# MIC_AND_SPEAKER.net
KiCad netlist of a schematic drawn in Altium Designer
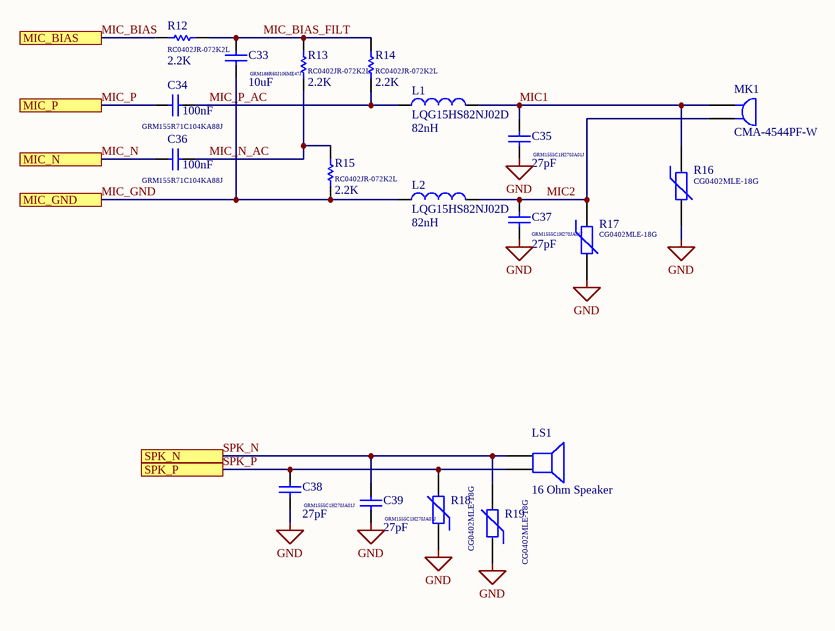
[diagram p0: MIC_AND_SPEAKER.SchDoc]

(export (version "E")
  (design (tool "Eeschema 10.0.6"))
  (components
    (comp (ref "C33")
      (value "GRM188R60J106ME47J")
      (footprint "0402")
      (description "Capacitor")
      (fields (field (name "ALTIUM_VALUE") "10uF") (field (name "PUBLISHER") "Altium Limited"))
      (libsource (lib "Miscellaneous Devices") (part "Cap"))
    )
    (comp (ref "C34")
      (value "GRM155R71C104KA88J")
      (footprint "0402")
      (description "Capacitor")
      (fields (field (name "ALTIUM_VALUE") "100nF") (field (name "PUBLISHER") "Altium Limited"))
      (libsource (lib "Miscellaneous Devices") (part "Cap"))
    )
    (comp (ref "C35")
      (value "GRM1555C1H270JA01J")
      (footprint "0402")
      (description "Capacitor")
      (fields (field (name "ALTIUM_VALUE") "27pF") (field (name "PUBLISHER") "Altium Limited"))
      (libsource (lib "Miscellaneous Devices") (part "Cap"))
    )
    (comp (ref "C36")
      (value "GRM155R71C104KA88J")
      (footprint "0402")
      (description "Capacitor")
      (fields (field (name "ALTIUM_VALUE") "100nF") (field (name "PUBLISHER") "Altium Limited"))
      (libsource (lib "Miscellaneous Devices") (part "Cap"))
    )
    (comp (ref "C37")
      (value "GRM1555C1H270JA01J")
      (footprint "0402")
      (description "Capacitor")
      (fields (field (name "ALTIUM_VALUE") "27pF") (field (name "PUBLISHER") "Altium Limited"))
      (libsource (lib "Miscellaneous Devices") (part "Cap"))
    )
    (comp (ref "C38")
      (value "GRM1555C1H270JA01J")
      (footprint "0402")
      (description "Capacitor")
      (fields (field (name "ALTIUM_VALUE") "27pF") (field (name "PUBLISHER") "Altium Limited"))
      (libsource (lib "Miscellaneous Devices") (part "Cap"))
    )
    (comp (ref "C39")
      (value "GRM1555C1H270JA01J")
      (footprint "0402")
      (description "Capacitor")
      (fields (field (name "ALTIUM_VALUE") "27pF") (field (name "PUBLISHER") "Altium Limited"))
      (libsource (lib "Miscellaneous Devices") (part "Cap"))
    )
    (comp (ref "L1")
      (value "LQG15HS82NJ02D")
      (footprint "0402-A")
      (description "Inductor")
      (fields (field (name "ALTIUM_VALUE") "82nH") (field (name "PUBLISHER") "Altium Limited"))
      (libsource (lib "Miscellaneous Devices") (part "Inductor"))
    )
    (comp (ref "L2")
      (value "LQG15HS82NJ02D")
      (footprint "0402-A")
      (description "Inductor")
      (fields (field (name "ALTIUM_VALUE") "82nH") (field (name "PUBLISHER") "Altium Limited"))
      (libsource (lib "Miscellaneous Devices") (part "Inductor"))
    )
    (comp (ref "LS1")
      (value "16 Ohm Speaker")
      (footprint "PIN2")
      (description "Loudspeaker")
      (fields (field (name "PUBLISHER") "Altium Limited"))
      (libsource (lib "Miscellaneous Devices") (part "Speaker"))
    )
    (comp (ref "MK1")
      (value "CMA-4544PF-W")
      (footprint "PIN2")
      (description "Microphone")
      (fields (field (name "PUBLISHER") "Altium Limited"))
      (libsource (lib "Miscellaneous Devices") (part "Mic1"))
    )
    (comp (ref "R12")
      (value "RC0402JR-072K2L")
      (footprint "0402")
      (description "Resistor")
      (fields (field (name "ALTIUM_VALUE") "2.2K") (field (name "PUBLISHER") "Altium Limited"))
      (libsource (lib "Miscellaneous Devices") (part "Res1"))
    )
    (comp (ref "R13")
      (value "RC0402JR-072K2L")
      (footprint "0402")
      (description "Resistor")
      (fields (field (name "ALTIUM_VALUE") "2.2K") (field (name "PUBLISHER") "Altium Limited"))
      (libsource (lib "Miscellaneous Devices") (part "Res1"))
    )
    (comp (ref "R14")
      (value "RC0402JR-072K2L")
      (footprint "0402")
      (description "Resistor")
      (fields (field (name "ALTIUM_VALUE") "2.2K") (field (name "PUBLISHER") "Altium Limited"))
      (libsource (lib "Miscellaneous Devices") (part "Res1"))
    )
    (comp (ref "R15")
      (value "RC0402JR-072K2L")
      (footprint "0402")
      (description "Resistor")
      (fields (field (name "ALTIUM_VALUE") "2.2K") (field (name "PUBLISHER") "Altium Limited"))
      (libsource (lib "Miscellaneous Devices") (part "Res1"))
    )
    (comp (ref "R16")
      (value "CG0402MLE-18G")
      (footprint "6-0805_N")
      (description "Varistor (Voltage-Sensitive Resistor)")
      (fields (field (name "PUBLISHER") "Altium Limited"))
      (libsource (lib "Miscellaneous Devices") (part "Res Varistor"))
    )
    (comp (ref "R17")
      (value "CG0402MLE-18G")
      (footprint "0402")
      (description "Varistor (Voltage-Sensitive Resistor)")
      (fields (field (name "PUBLISHER") "Altium Limited"))
      (libsource (lib "Miscellaneous Devices") (part "Res Varistor"))
    )
    (comp (ref "R18")
      (value "CG0402MLE-18G")
      (footprint "0402")
      (description "Varistor (Voltage-Sensitive Resistor)")
      (fields (field (name "PUBLISHER") "Altium Limited"))
      (libsource (lib "Miscellaneous Devices") (part "Res Varistor"))
    )
    (comp (ref "R19")
      (value "CG0402MLE-18G")
      (footprint "0402")
      (description "Varistor (Voltage-Sensitive Resistor)")
      (fields (field (name "PUBLISHER") "Altium Limited"))
      (libsource (lib "Miscellaneous Devices") (part "Res Varistor"))
    )
  )
  (nets
    (net (code "1") (name "/MIC1") (class "Default")
      (node (ref "C35") (pin "2") (pinfunction "2_2") (pintype "passive"))
      (node (ref "L1") (pin "2") (pinfunction "2_2") (pintype "passive"))
      (node (ref "MK1") (pin "1") (pinfunction "1_1") (pintype "passive"))
      (node (ref "R16") (pin "1") (pinfunction "1_1") (pintype "passive"))
    )
    (net (code "2") (name "/MIC2") (class "Default")
      (node (ref "C37") (pin "2") (pinfunction "2_2") (pintype "passive"))
      (node (ref "L2") (pin "2") (pinfunction "2_2") (pintype "passive"))
      (node (ref "MK1") (pin "2") (pinfunction "2_2") (pintype "passive"))
      (node (ref "R17") (pin "1") (pinfunction "1_1") (pintype "passive"))
    )
    (net (code "3") (name "/MIC_BIAS") (class "Default")
      (node (ref "R12") (pin "2") (pinfunction "2_2") (pintype "passive"))
    )
    (net (code "4") (name "/MIC_BIAS_FILT") (class "Default")
      (node (ref "C33") (pin "2") (pinfunction "2_2") (pintype "passive"))
      (node (ref "R12") (pin "1") (pinfunction "1_1") (pintype "passive"))
      (node (ref "R13") (pin "2") (pinfunction "2_2") (pintype "passive"))
      (node (ref "R14") (pin "2") (pinfunction "2_2") (pintype "passive"))
    )
    (net (code "5") (name "/MIC_GND") (class "Default")
      (node (ref "C33") (pin "1") (pinfunction "1_1") (pintype "passive"))
      (node (ref "L2") (pin "1") (pinfunction "1_1") (pintype "passive"))
      (node (ref "R15") (pin "1") (pinfunction "1_1") (pintype "passive"))
    )
    (net (code "6") (name "/MIC_N") (class "Default")
      (node (ref "C36") (pin "2") (pinfunction "2_2") (pintype "passive"))
    )
    (net (code "7") (name "/MIC_N_AC") (class "Default")
      (node (ref "C36") (pin "1") (pinfunction "1_1") (pintype "passive"))
      (node (ref "R13") (pin "1") (pinfunction "1_1") (pintype "passive"))
      (node (ref "R15") (pin "2") (pinfunction "2_2") (pintype "passive"))
    )
    (net (code "8") (name "/MIC_P") (class "Default")
      (node (ref "C34") (pin "2") (pinfunction "2_2") (pintype "passive"))
    )
    (net (code "9") (name "/MIC_P_AC") (class "Default")
      (node (ref "C34") (pin "1") (pinfunction "1_1") (pintype "passive"))
      (node (ref "L1") (pin "1") (pinfunction "1_1") (pintype "passive"))
      (node (ref "R14") (pin "1") (pinfunction "1_1") (pintype "passive"))
    )
    (net (code "10") (name "/SPK_N") (class "Default")
      (node (ref "C39") (pin "2") (pinfunction "2_2") (pintype "passive"))
      (node (ref "LS1") (pin "1") (pinfunction "1_1") (pintype "passive"))
      (node (ref "R19") (pin "2") (pinfunction "2_2") (pintype "passive"))
    )
    (net (code "11") (name "/SPK_P") (class "Default")
      (node (ref "C38") (pin "2") (pinfunction "2_2") (pintype "passive"))
      (node (ref "LS1") (pin "2") (pinfunction "2_2") (pintype "passive"))
      (node (ref "R18") (pin "2") (pinfunction "2_2") (pintype "passive"))
    )
    (net (code "12") (name "GND") (class "Default")
      (node (ref "C35") (pin "1") (pinfunction "1_1") (pintype "passive"))
      (node (ref "C37") (pin "1") (pinfunction "1_1") (pintype "passive"))
      (node (ref "C38") (pin "1") (pinfunction "1_1") (pintype "passive"))
      (node (ref "C39") (pin "1") (pinfunction "1_1") (pintype "passive"))
      (node (ref "R16") (pin "2") (pinfunction "2_2") (pintype "passive"))
      (node (ref "R17") (pin "2") (pinfunction "2_2") (pintype "passive"))
      (node (ref "R18") (pin "1") (pinfunction "1_1") (pintype "passive"))
      (node (ref "R19") (pin "1") (pinfunction "1_1") (pintype "passive"))
    )
  )
)
